# 5_cyber60-alps_periferals.net
KiCad netlist of a schematic drawn in Altium Designer
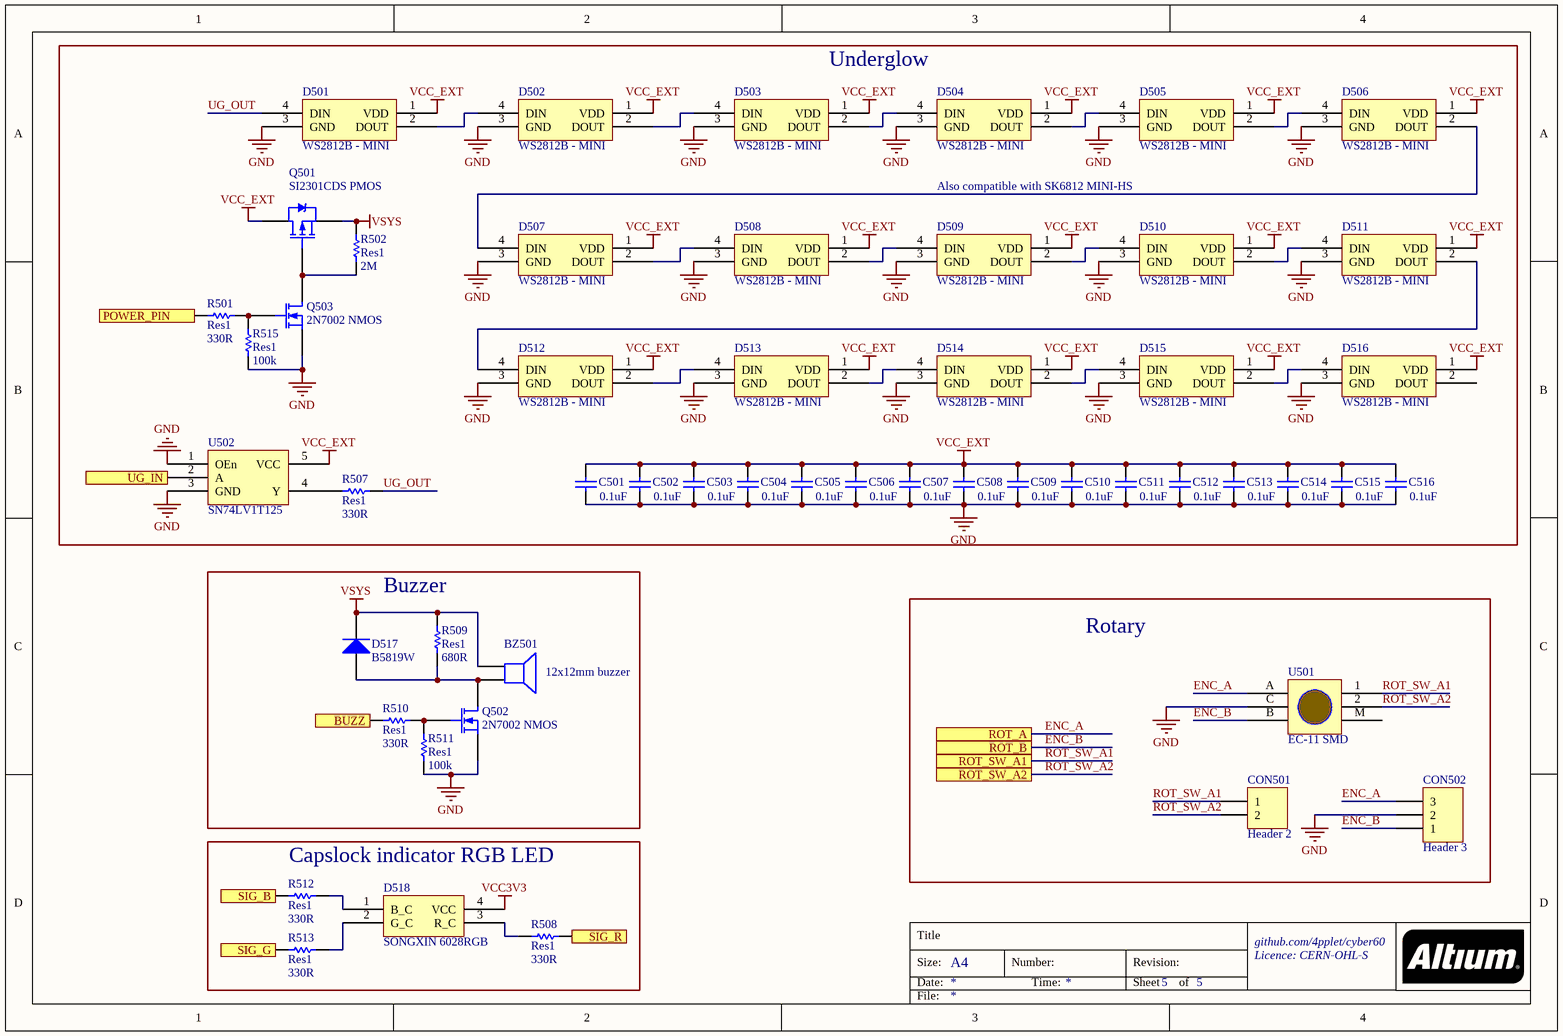
[diagram p0: 5_cyber60-alps_periferals.SchDoc]

(export (version "E")
  (design (tool "Eeschema 10.0.6"))
  (components
    (comp (ref "BZ501")
      (value "12x12mm buzzer")
      (footprint "buzzer 12x12")
      (description "Loudspeaker")
      (fields (field (name "LCSC PART #") "C409829") (field (name "MRF.PART") "YS-SBZ1230"))
      (libsource (lib "Miscellaneous Devices") (part "Speaker"))
    )
    (comp (ref "C501")
      (value "0.1uF")
      (footprint "C0603[1608]")
      (description "Capacitor")
      (fields (field (name "MFG") "KEMET") (field (name "LCSC PART #") "C14663"))
      (libsource (lib "Miscellaneous Devices") (part "Cap"))
    )
    (comp (ref "C502")
      (value "0.1uF")
      (footprint "C0603[1608]")
      (description "Capacitor")
      (fields (field (name "MFG") "KEMET") (field (name "LCSC PART #") "C14663"))
      (libsource (lib "Miscellaneous Devices") (part "Cap"))
    )
    (comp (ref "C503")
      (value "0.1uF")
      (footprint "C0603[1608]")
      (description "Capacitor")
      (fields (field (name "MFG") "KEMET") (field (name "LCSC PART #") "C14663"))
      (libsource (lib "Miscellaneous Devices") (part "Cap"))
    )
    (comp (ref "C504")
      (value "0.1uF")
      (footprint "C0603[1608]")
      (description "Capacitor")
      (fields (field (name "MFG") "KEMET") (field (name "LCSC PART #") "C14663"))
      (libsource (lib "Miscellaneous Devices") (part "Cap"))
    )
    (comp (ref "C505")
      (value "0.1uF")
      (footprint "C0603[1608]")
      (description "Capacitor")
      (fields (field (name "MFG") "KEMET") (field (name "LCSC PART #") "C14663"))
      (libsource (lib "Miscellaneous Devices") (part "Cap"))
    )
    (comp (ref "C506")
      (value "0.1uF")
      (footprint "C0603[1608]")
      (description "Capacitor")
      (fields (field (name "MFG") "KEMET") (field (name "LCSC PART #") "C14663"))
      (libsource (lib "Miscellaneous Devices") (part "Cap"))
    )
    (comp (ref "C507")
      (value "0.1uF")
      (footprint "C0603[1608]")
      (description "Capacitor")
      (fields (field (name "MFG") "KEMET") (field (name "LCSC PART #") "C14663"))
      (libsource (lib "Miscellaneous Devices") (part "Cap"))
    )
    (comp (ref "C508")
      (value "0.1uF")
      (footprint "C0603[1608]")
      (description "Capacitor")
      (fields (field (name "MFG") "KEMET") (field (name "LCSC PART #") "C14663"))
      (libsource (lib "Miscellaneous Devices") (part "Cap"))
    )
    (comp (ref "C509")
      (value "0.1uF")
      (footprint "C0603[1608]")
      (description "Capacitor")
      (fields (field (name "MFG") "KEMET") (field (name "LCSC PART #") "C14663"))
      (libsource (lib "Miscellaneous Devices") (part "Cap"))
    )
    (comp (ref "C510")
      (value "0.1uF")
      (footprint "C0603[1608]")
      (description "Capacitor")
      (fields (field (name "MFG") "KEMET") (field (name "LCSC PART #") "C14663"))
      (libsource (lib "Miscellaneous Devices") (part "Cap"))
    )
    (comp (ref "C511")
      (value "0.1uF")
      (footprint "C0603[1608]")
      (description "Capacitor")
      (fields (field (name "MFG") "KEMET") (field (name "LCSC PART #") "C14663"))
      (libsource (lib "Miscellaneous Devices") (part "Cap"))
    )
    (comp (ref "C512")
      (value "0.1uF")
      (footprint "C0603[1608]")
      (description "Capacitor")
      (fields (field (name "MFG") "KEMET") (field (name "LCSC PART #") "C14663"))
      (libsource (lib "Miscellaneous Devices") (part "Cap"))
    )
    (comp (ref "C513")
      (value "0.1uF")
      (footprint "C0603[1608]")
      (description "Capacitor")
      (fields (field (name "MFG") "KEMET") (field (name "LCSC PART #") "C14663"))
      (libsource (lib "Miscellaneous Devices") (part "Cap"))
    )
    (comp (ref "C514")
      (value "0.1uF")
      (footprint "C0603[1608]")
      (description "Capacitor")
      (fields (field (name "MFG") "KEMET") (field (name "LCSC PART #") "C14663"))
      (libsource (lib "Miscellaneous Devices") (part "Cap"))
    )
    (comp (ref "C515")
      (value "0.1uF")
      (footprint "C0603[1608]")
      (description "Capacitor")
      (fields (field (name "MFG") "KEMET") (field (name "LCSC PART #") "C14663"))
      (libsource (lib "Miscellaneous Devices") (part "Cap"))
    )
    (comp (ref "C516")
      (value "0.1uF")
      (footprint "C0603[1608]")
      (description "Capacitor")
      (fields (field (name "MFG") "KEMET") (field (name "LCSC PART #") "C14663"))
      (libsource (lib "Miscellaneous Devices") (part "Cap"))
    )
    (comp (ref "CON501")
      (value "Header 2")
      (footprint "HDR1X2")
      (description "Header, 2-Pin")
      (libsource (lib "Miscellaneous Connectors") (part "Header 2"))
    )
    (comp (ref "CON502")
      (value "Header 3")
      (footprint "HDR1X3")
      (description "Header, 3-Pin")
      (libsource (lib "Miscellaneous Connectors") (part "Header 3"))
    )
    (comp (ref "D501")
      (value "WS2812B - MINI")
      (footprint "WS2812B - 2020")
      (fields (field (name "LCSC PART #") "C965556") (field (name "MRF.PART") "WS2812C-2020"))
      (libsource (lib "Keebs") (part "WS2812B"))
    )
    (comp (ref "D502")
      (value "WS2812B - MINI")
      (footprint "WS2812B - 2020")
      (fields (field (name "LCSC PART #") "C965556") (field (name "MRF.PART") "WS2812C-2020"))
      (libsource (lib "Keebs") (part "WS2812B"))
    )
    (comp (ref "D503")
      (value "WS2812B - MINI")
      (footprint "WS2812B - 2020")
      (fields (field (name "LCSC PART #") "C965556") (field (name "MRF.PART") "WS2812C-2020"))
      (libsource (lib "Keebs") (part "WS2812B"))
    )
    (comp (ref "D504")
      (value "WS2812B - MINI")
      (footprint "WS2812B - 2020")
      (fields (field (name "LCSC PART #") "C965556") (field (name "MRF.PART") "WS2812C-2020"))
      (libsource (lib "Keebs") (part "WS2812B"))
    )
    (comp (ref "D505")
      (value "WS2812B - MINI")
      (footprint "WS2812B - 2020")
      (fields (field (name "LCSC PART #") "C965556") (field (name "MRF.PART") "WS2812C-2020"))
      (libsource (lib "Keebs") (part "WS2812B"))
    )
    (comp (ref "D506")
      (value "WS2812B - MINI")
      (footprint "WS2812B - 2020")
      (fields (field (name "LCSC PART #") "C965556") (field (name "MRF.PART") "WS2812C-2020"))
      (libsource (lib "Keebs") (part "WS2812B"))
    )
    (comp (ref "D507")
      (value "WS2812B - MINI")
      (footprint "WS2812B - 2020")
      (fields (field (name "LCSC PART #") "C965556") (field (name "MRF.PART") "WS2812C-2020"))
      (libsource (lib "Keebs") (part "WS2812B"))
    )
    (comp (ref "D508")
      (value "WS2812B - MINI")
      (footprint "WS2812B - 2020")
      (fields (field (name "LCSC PART #") "C965556") (field (name "MRF.PART") "WS2812C-2020"))
      (libsource (lib "Keebs") (part "WS2812B"))
    )
    (comp (ref "D509")
      (value "WS2812B - MINI")
      (footprint "WS2812B - 2020")
      (fields (field (name "LCSC PART #") "C965556") (field (name "MRF.PART") "WS2812C-2020"))
      (libsource (lib "Keebs") (part "WS2812B"))
    )
    (comp (ref "D510")
      (value "WS2812B - MINI")
      (footprint "WS2812B - 2020")
      (fields (field (name "LCSC PART #") "C965556") (field (name "MRF.PART") "WS2812C-2020"))
      (libsource (lib "Keebs") (part "WS2812B"))
    )
    (comp (ref "D511")
      (value "WS2812B - MINI")
      (footprint "WS2812B - 2020")
      (fields (field (name "LCSC PART #") "C965556") (field (name "MRF.PART") "WS2812C-2020"))
      (libsource (lib "Keebs") (part "WS2812B"))
    )
    (comp (ref "D512")
      (value "WS2812B - MINI")
      (footprint "WS2812B - 2020")
      (fields (field (name "LCSC PART #") "C965556") (field (name "MRF.PART") "WS2812C-2020"))
      (libsource (lib "Keebs") (part "WS2812B"))
    )
    (comp (ref "D513")
      (value "WS2812B - MINI")
      (footprint "WS2812B - 2020")
      (fields (field (name "LCSC PART #") "C965556") (field (name "MRF.PART") "WS2812C-2020"))
      (libsource (lib "Keebs") (part "WS2812B"))
    )
    (comp (ref "D514")
      (value "WS2812B - MINI")
      (footprint "WS2812B - 2020")
      (fields (field (name "LCSC PART #") "C965556") (field (name "MRF.PART") "WS2812C-2020"))
      (libsource (lib "Keebs") (part "WS2812B"))
    )
    (comp (ref "D515")
      (value "WS2812B - MINI")
      (footprint "WS2812B - 2020")
      (fields (field (name "LCSC PART #") "C965556") (field (name "MRF.PART") "WS2812C-2020"))
      (libsource (lib "Keebs") (part "WS2812B"))
    )
    (comp (ref "D516")
      (value "WS2812B - MINI")
      (footprint "WS2812B - 2020")
      (fields (field (name "LCSC PART #") "C965556") (field (name "MRF.PART") "WS2812C-2020"))
      (libsource (lib "Keebs") (part "WS2812B"))
    )
    (comp (ref "D517")
      (value "B5819W")
      (footprint "SOD-123")
      (description "Default Diode")
      (fields (field (name "LCSC PART #") "C8598"))
      (libsource (lib "Miscellaneous Devices") (part "Diode"))
    )
    (comp (ref "D518")
      (value "SONGXIN 6028RGB")
      (footprint "SONGXIN 6028RGB")
      (libsource (lib "Keebs") (part "SONGXIN 6028RGB"))
    )
    (comp (ref "Q501")
      (value "SI2301CDS PMOS")
      (footprint "SOT-23-3")
      (description "P-Channel Power MOSFET")
      (fields (field (name "MRF.PART") "SI2301CDS-T1-GE3") (field (name "LCSC PART #") "C10487"))
      (libsource (lib "Miscellaneous Devices") (part "PMOS-2"))
    )
    (comp (ref "Q502")
      (value "2N7002 NMOS")
      (footprint "SOT-23-3")
      (description "N-Channel MOSFET")
      (fields (field (name "LCSC PART #") "C8545") (field (name "MRF.PART") "2N7002"))
      (libsource (lib "Miscellaneous Devices") (part "MOSFET-N"))
    )
    (comp (ref "Q503")
      (value "2N7002 NMOS")
      (footprint "SOT-23-3")
      (description "N-Channel MOSFET")
      (fields (field (name "LCSC PART #") "C8545") (field (name "MRF.PART") "2N7002"))
      (libsource (lib "Miscellaneous Devices") (part "MOSFET-N"))
    )
    (comp (ref "R501")
      (value "Res1")
      (footprint "R0603[1608]")
      (description "Resistor")
      (fields
        (field (name "ALTIUM_VALUE") "330R")
        (field (name "LCSC PART #") "C23138")
        (field (name "MRF.PART") "0603WAF3300T5E")
      )
      (libsource (lib "Miscellaneous Devices") (part "Res1"))
    )
    (comp (ref "R502")
      (value "Res1")
      (footprint "R0603[1608]")
      (description "Resistor")
      (fields
        (field (name "ALTIUM_VALUE") "2M")
        (field (name "MRF.PART") "0603WAF2004T5E")
        (field (name "LCSC PART #") "C22976")
      )
      (libsource (lib "Miscellaneous Devices") (part "Res1"))
    )
    (comp (ref "R507")
      (value "Res1")
      (footprint "R0603[1608]")
      (description "Resistor")
      (fields
        (field (name "ALTIUM_VALUE") "330R")
        (field (name "LCSC PART #") "C23138")
        (field (name "MRF.PART") "0603WAF3300T5E")
      )
      (libsource (lib "Miscellaneous Devices") (part "Res1"))
    )
    (comp (ref "R508")
      (value "Res1")
      (footprint "R0603[1608]")
      (description "Resistor")
      (fields
        (field (name "ALTIUM_VALUE") "330R")
        (field (name "LCSC PART #") "C23138")
        (field (name "MRF.PART") "0603WAF3300T5E")
      )
      (libsource (lib "Miscellaneous Devices") (part "Res1"))
    )
    (comp (ref "R509")
      (value "Res1")
      (footprint "R0603[1608]")
      (description "Resistor")
      (fields
        (field (name "ALTIUM_VALUE") "680R")
        (field (name "MRF.PART") "0603WAF6800T5E")
        (field (name "LCSC PART #") "C23228")
      )
      (libsource (lib "Miscellaneous Devices") (part "Res1"))
    )
    (comp (ref "R510")
      (value "Res1")
      (footprint "R0603[1608]")
      (description "Resistor")
      (fields
        (field (name "ALTIUM_VALUE") "330R")
        (field (name "LCSC PART #") "C23138")
        (field (name "MRF.PART") "0603WAF3300T5E")
      )
      (libsource (lib "Miscellaneous Devices") (part "Res1"))
    )
    (comp (ref "R511")
      (value "Res1")
      (footprint "R0603[1608]")
      (description "Resistor")
      (fields
        (field (name "ALTIUM_VALUE") "100k")
        (field (name "MRF.PART") "0603WAF1003T5E")
        (field (name "LCSC PART #") "C25803")
      )
      (libsource (lib "Miscellaneous Devices") (part "Res1"))
    )
    (comp (ref "R512")
      (value "Res1")
      (footprint "R0603[1608]")
      (description "Resistor")
      (fields
        (field (name "ALTIUM_VALUE") "330R")
        (field (name "LCSC PART #") "C23138")
        (field (name "MRF.PART") "0603WAF3300T5E")
      )
      (libsource (lib "Miscellaneous Devices") (part "Res1"))
    )
    (comp (ref "R513")
      (value "Res1")
      (footprint "R0603[1608]")
      (description "Resistor")
      (fields
        (field (name "ALTIUM_VALUE") "330R")
        (field (name "LCSC PART #") "C23138")
        (field (name "MRF.PART") "0603WAF3300T5E")
      )
      (libsource (lib "Miscellaneous Devices") (part "Res1"))
    )
    (comp (ref "R515")
      (value "Res1")
      (footprint "R0603[1608]")
      (description "Resistor")
      (fields
        (field (name "ALTIUM_VALUE") "100k")
        (field (name "MRF.PART") "0603WAF1003T5E")
        (field (name "LCSC PART #") "C25803")
      )
      (libsource (lib "Miscellaneous Devices") (part "Res1"))
    )
    (comp (ref "U501") (value "EC-11 SMD") (footprint "EC11-SMD") (libsource (lib "Keebs") (part "EC-11")))
    (comp (ref "U502")
      (value "SN74LV1T125")
      (footprint "SOT-23-5")
      (description "SN74LV1T125 or SN74LV1T34. Connect OE to GND")
      (fields (field (name "LCSC PART #") "C473338") (field (name "MRF.PART") "SN74LV1T125DBVR"))
      (libsource (lib "Keebs") (part "SN74LV1T125"))
    )
  )
  (nets
    (net (code "1") (name "/BUZZ") (class "Default")
      (node (ref "R510") (pin "2") (pinfunction "2_2") (pintype "passive"))
    )
    (net (code "2") (name "/ENC_A") (class "Default")
      (node (ref "CON502") (pin "3") (pinfunction "3_3") (pintype "passive"))
      (node (ref "U501") (pin "A") (pinfunction "B_A") (pintype "passive"))
    )
    (net (code "3") (name "/ENC_B") (class "Default")
      (node (ref "CON502") (pin "1") (pinfunction "1_1") (pintype "passive"))
      (node (ref "U501") (pin "B") (pinfunction "B_B") (pintype "passive"))
    )
    (net (code "4") (name "/POWER_PIN") (class "Default")
      (node (ref "R501") (pin "1") (pinfunction "1_1") (pintype "passive"))
    )
    (net (code "5") (name "/ROT_SW_A1") (class "Default")
      (node (ref "CON501") (pin "1") (pinfunction "1_1") (pintype "passive"))
      (node (ref "U501") (pin "1") (pinfunction "1_1") (pintype "passive"))
    )
    (net (code "6") (name "/ROT_SW_A2") (class "Default")
      (node (ref "CON501") (pin "2") (pinfunction "2_2") (pintype "passive"))
      (node (ref "U501") (pin "2") (pinfunction "2_2") (pintype "passive"))
    )
    (net (code "7") (name "/SIG_B") (class "Default")
      (node (ref "R512") (pin "2") (pinfunction "2_2") (pintype "passive"))
    )
    (net (code "8") (name "/SIG_G") (class "Default")
      (node (ref "R513") (pin "2") (pinfunction "2_2") (pintype "passive"))
    )
    (net (code "9") (name "/SIG_R") (class "Default")
      (node (ref "R508") (pin "1") (pinfunction "1_1") (pintype "passive"))
    )
    (net (code "10") (name "/UG_IN") (class "Default")
      (node (ref "U502") (pin "2") (pinfunction "A_2") (pintype "passive"))
    )
    (net (code "11") (name "/UG_OUT") (class "Default")
      (node (ref "D501") (pin "4") (pinfunction "DIN_4") (pintype "passive"))
      (node (ref "R507") (pin "1") (pinfunction "1_1") (pintype "passive"))
    )
    (net (code "12") (name "GND") (class "Default")
      (node (ref "C501") (pin "1") (pinfunction "1_1") (pintype "passive"))
      (node (ref "C502") (pin "1") (pinfunction "1_1") (pintype "passive"))
      (node (ref "C503") (pin "1") (pinfunction "1_1") (pintype "passive"))
      (node (ref "C504") (pin "1") (pinfunction "1_1") (pintype "passive"))
      (node (ref "C505") (pin "1") (pinfunction "1_1") (pintype "passive"))
      (node (ref "C506") (pin "1") (pinfunction "1_1") (pintype "passive"))
      (node (ref "C507") (pin "1") (pinfunction "1_1") (pintype "passive"))
      (node (ref "C508") (pin "1") (pinfunction "1_1") (pintype "passive"))
      (node (ref "C509") (pin "1") (pinfunction "1_1") (pintype "passive"))
      (node (ref "C510") (pin "1") (pinfunction "1_1") (pintype "passive"))
      (node (ref "C511") (pin "1") (pinfunction "1_1") (pintype "passive"))
      (node (ref "C512") (pin "1") (pinfunction "1_1") (pintype "passive"))
      (node (ref "C513") (pin "1") (pinfunction "1_1") (pintype "passive"))
      (node (ref "C514") (pin "1") (pinfunction "1_1") (pintype "passive"))
      (node (ref "C515") (pin "1") (pinfunction "1_1") (pintype "passive"))
      (node (ref "C516") (pin "1") (pinfunction "1_1") (pintype "passive"))
      (node (ref "CON502") (pin "2") (pinfunction "2_2") (pintype "passive"))
      (node (ref "D501") (pin "3") (pinfunction "GND_3") (pintype "passive"))
      (node (ref "D502") (pin "3") (pinfunction "GND_3") (pintype "passive"))
      (node (ref "D503") (pin "3") (pinfunction "GND_3") (pintype "passive"))
      (node (ref "D504") (pin "3") (pinfunction "GND_3") (pintype "passive"))
      (node (ref "D505") (pin "3") (pinfunction "GND_3") (pintype "passive"))
      (node (ref "D506") (pin "3") (pinfunction "GND_3") (pintype "passive"))
      (node (ref "D507") (pin "3") (pinfunction "GND_3") (pintype "passive"))
      (node (ref "D508") (pin "3") (pinfunction "GND_3") (pintype "passive"))
      (node (ref "D509") (pin "3") (pinfunction "GND_3") (pintype "passive"))
      (node (ref "D510") (pin "3") (pinfunction "GND_3") (pintype "passive"))
      (node (ref "D511") (pin "3") (pinfunction "GND_3") (pintype "passive"))
      (node (ref "D512") (pin "3") (pinfunction "GND_3") (pintype "passive"))
      (node (ref "D513") (pin "3") (pinfunction "GND_3") (pintype "passive"))
      (node (ref "D514") (pin "3") (pinfunction "GND_3") (pintype "passive"))
      (node (ref "D515") (pin "3") (pinfunction "GND_3") (pintype "passive"))
      (node (ref "D516") (pin "3") (pinfunction "GND_3") (pintype "passive"))
      (node (ref "Q502") (pin "2") (pinfunction "S_2") (pintype "passive"))
      (node (ref "Q503") (pin "2") (pinfunction "S_2") (pintype "passive"))
      (node (ref "R511") (pin "2") (pinfunction "2_2") (pintype "passive"))
      (node (ref "R515") (pin "2") (pinfunction "2_2") (pintype "passive"))
      (node (ref "U501") (pin "C") (pinfunction "C_C") (pintype "passive"))
      (node (ref "U502") (pin "1") (pinfunction "OEn_1") (pintype "passive"))
      (node (ref "U502") (pin "3") (pinfunction "GND_3") (pintype "passive"))
    )
    (net (code "13") (name "Net-(D501-DOUT)") (class "Default")
      (node (ref "D501") (pin "2") (pinfunction "DOUT_2") (pintype "passive"))
      (node (ref "D502") (pin "4") (pinfunction "DIN_4") (pintype "passive"))
    )
    (net (code "14") (name "Net-(D502-DOUT)") (class "Default")
      (node (ref "D502") (pin "2") (pinfunction "DOUT_2") (pintype "passive"))
      (node (ref "D503") (pin "4") (pinfunction "DIN_4") (pintype "passive"))
    )
    (net (code "15") (name "Net-(D503-DOUT)") (class "Default")
      (node (ref "D503") (pin "2") (pinfunction "DOUT_2") (pintype "passive"))
      (node (ref "D504") (pin "4") (pinfunction "DIN_4") (pintype "passive"))
    )
    (net (code "16") (name "Net-(D504-DOUT)") (class "Default")
      (node (ref "D504") (pin "2") (pinfunction "DOUT_2") (pintype "passive"))
      (node (ref "D505") (pin "4") (pinfunction "DIN_4") (pintype "passive"))
    )
    (net (code "17") (name "Net-(D505-DOUT)") (class "Default")
      (node (ref "D505") (pin "2") (pinfunction "DOUT_2") (pintype "passive"))
      (node (ref "D506") (pin "4") (pinfunction "DIN_4") (pintype "passive"))
    )
    (net (code "18") (name "Net-(D506-DOUT)") (class "Default")
      (node (ref "D506") (pin "2") (pinfunction "DOUT_2") (pintype "passive"))
      (node (ref "D507") (pin "4") (pinfunction "DIN_4") (pintype "passive"))
    )
    (net (code "19") (name "Net-(D507-DOUT)") (class "Default")
      (node (ref "D507") (pin "2") (pinfunction "DOUT_2") (pintype "passive"))
      (node (ref "D508") (pin "4") (pinfunction "DIN_4") (pintype "passive"))
    )
    (net (code "20") (name "Net-(D508-DOUT)") (class "Default")
      (node (ref "D508") (pin "2") (pinfunction "DOUT_2") (pintype "passive"))
      (node (ref "D509") (pin "4") (pinfunction "DIN_4") (pintype "passive"))
    )
    (net (code "21") (name "Net-(D509-DOUT)") (class "Default")
      (node (ref "D509") (pin "2") (pinfunction "DOUT_2") (pintype "passive"))
      (node (ref "D510") (pin "4") (pinfunction "DIN_4") (pintype "passive"))
    )
    (net (code "22") (name "Net-(D510-DOUT)") (class "Default")
      (node (ref "D510") (pin "2") (pinfunction "DOUT_2") (pintype "passive"))
      (node (ref "D511") (pin "4") (pinfunction "DIN_4") (pintype "passive"))
    )
    (net (code "23") (name "Net-(D511-DOUT)") (class "Default")
      (node (ref "D511") (pin "2") (pinfunction "DOUT_2") (pintype "passive"))
      (node (ref "D512") (pin "4") (pinfunction "DIN_4") (pintype "passive"))
    )
    (net (code "24") (name "Net-(D512-DOUT)") (class "Default")
      (node (ref "D512") (pin "2") (pinfunction "DOUT_2") (pintype "passive"))
      (node (ref "D513") (pin "4") (pinfunction "DIN_4") (pintype "passive"))
    )
    (net (code "25") (name "Net-(D513-DOUT)") (class "Default")
      (node (ref "D513") (pin "2") (pinfunction "DOUT_2") (pintype "passive"))
      (node (ref "D514") (pin "4") (pinfunction "DIN_4") (pintype "passive"))
    )
    (net (code "26") (name "Net-(D514-DOUT)") (class "Default")
      (node (ref "D514") (pin "2") (pinfunction "DOUT_2") (pintype "passive"))
      (node (ref "D515") (pin "4") (pinfunction "DIN_4") (pintype "passive"))
    )
    (net (code "27") (name "Net-(D515-DOUT)") (class "Default")
      (node (ref "D515") (pin "2") (pinfunction "DOUT_2") (pintype "passive"))
      (node (ref "D516") (pin "4") (pinfunction "DIN_4") (pintype "passive"))
    )
    (net (code "28") (name "Net-(D517-A)") (class "Default")
      (node (ref "BZ501") (pin "2") (pinfunction "2_2") (pintype "passive"))
      (node (ref "D517") (pin "1") (pinfunction "A_1") (pintype "passive"))
      (node (ref "Q502") (pin "3") (pinfunction "D_3") (pintype "passive"))
      (node (ref "R509") (pin "2") (pinfunction "2_2") (pintype "passive"))
    )
    (net (code "29") (name "Net-(D518-B_C)") (class "Default")
      (node (ref "D518") (pin "1") (pinfunction "B_C_1") (pintype "passive"))
      (node (ref "R512") (pin "1") (pinfunction "1_1") (pintype "passive"))
    )
    (net (code "30") (name "Net-(D518-G_C)") (class "Default")
      (node (ref "D518") (pin "2") (pinfunction "G_C_2") (pintype "passive"))
      (node (ref "R513") (pin "1") (pinfunction "1_1") (pintype "passive"))
    )
    (net (code "31") (name "Net-(D518-R_C)") (class "Default")
      (node (ref "D518") (pin "3") (pinfunction "R_C_3") (pintype "passive"))
      (node (ref "R508") (pin "2") (pinfunction "2_2") (pintype "passive"))
    )
    (net (code "32") (name "Net-(Q501-G)") (class "Default")
      (node (ref "Q501") (pin "1") (pinfunction "G_1") (pintype "passive"))
      (node (ref "Q503") (pin "3") (pinfunction "D_3") (pintype "passive"))
      (node (ref "R502") (pin "1") (pinfunction "1_1") (pintype "passive"))
    )
    (net (code "33") (name "Net-(Q502-G)") (class "Default")
      (node (ref "Q502") (pin "1") (pinfunction "G_1") (pintype "passive"))
      (node (ref "R510") (pin "1") (pinfunction "1_1") (pintype "passive"))
      (node (ref "R511") (pin "1") (pinfunction "1_1") (pintype "passive"))
    )
    (net (code "34") (name "Net-(Q503-G)") (class "Default")
      (node (ref "Q503") (pin "1") (pinfunction "G_1") (pintype "passive"))
      (node (ref "R501") (pin "2") (pinfunction "2_2") (pintype "passive"))
      (node (ref "R515") (pin "1") (pinfunction "1_1") (pintype "passive"))
    )
    (net (code "35") (name "Net-(U502-Y)") (class "Default")
      (node (ref "R507") (pin "2") (pinfunction "2_2") (pintype "passive"))
      (node (ref "U502") (pin "4") (pinfunction "Y_4") (pintype "passive"))
    )
    (net (code "36") (name "VCC3V3") (class "Default")
      (node (ref "D518") (pin "4") (pinfunction "VCC_4") (pintype "passive"))
    )
    (net (code "37") (name "VCC_EXT") (class "Default")
      (node (ref "C501") (pin "2") (pinfunction "2_2") (pintype "passive"))
      (node (ref "C502") (pin "2") (pinfunction "2_2") (pintype "passive"))
      (node (ref "C503") (pin "2") (pinfunction "2_2") (pintype "passive"))
      (node (ref "C504") (pin "2") (pinfunction "2_2") (pintype "passive"))
      (node (ref "C505") (pin "2") (pinfunction "2_2") (pintype "passive"))
      (node (ref "C506") (pin "2") (pinfunction "2_2") (pintype "passive"))
      (node (ref "C507") (pin "2") (pinfunction "2_2") (pintype "passive"))
      (node (ref "C508") (pin "2") (pinfunction "2_2") (pintype "passive"))
      (node (ref "C509") (pin "2") (pinfunction "2_2") (pintype "passive"))
      (node (ref "C510") (pin "2") (pinfunction "2_2") (pintype "passive"))
      (node (ref "C511") (pin "2") (pinfunction "2_2") (pintype "passive"))
      (node (ref "C512") (pin "2") (pinfunction "2_2") (pintype "passive"))
      (node (ref "C513") (pin "2") (pinfunction "2_2") (pintype "passive"))
      (node (ref "C514") (pin "2") (pinfunction "2_2") (pintype "passive"))
      (node (ref "C515") (pin "2") (pinfunction "2_2") (pintype "passive"))
      (node (ref "C516") (pin "2") (pinfunction "2_2") (pintype "passive"))
      (node (ref "D501") (pin "1") (pinfunction "VDD_1") (pintype "passive"))
      (node (ref "D502") (pin "1") (pinfunction "VDD_1") (pintype "passive"))
      (node (ref "D503") (pin "1") (pinfunction "VDD_1") (pintype "passive"))
      (node (ref "D504") (pin "1") (pinfunction "VDD_1") (pintype "passive"))
      (node (ref "D505") (pin "1") (pinfunction "VDD_1") (pintype "passive"))
      (node (ref "D506") (pin "1") (pinfunction "VDD_1") (pintype "passive"))
      (node (ref "D507") (pin "1") (pinfunction "VDD_1") (pintype "passive"))
      (node (ref "D508") (pin "1") (pinfunction "VDD_1") (pintype "passive"))
      (node (ref "D509") (pin "1") (pinfunction "VDD_1") (pintype "passive"))
      (node (ref "D510") (pin "1") (pinfunction "VDD_1") (pintype "passive"))
      (node (ref "D511") (pin "1") (pinfunction "VDD_1") (pintype "passive"))
      (node (ref "D512") (pin "1") (pinfunction "VDD_1") (pintype "passive"))
      (node (ref "D513") (pin "1") (pinfunction "VDD_1") (pintype "passive"))
      (node (ref "D514") (pin "1") (pinfunction "VDD_1") (pintype "passive"))
      (node (ref "D515") (pin "1") (pinfunction "VDD_1") (pintype "passive"))
      (node (ref "D516") (pin "1") (pinfunction "VDD_1") (pintype "passive"))
      (node (ref "Q501") (pin "3") (pinfunction "D_3") (pintype "passive"))
      (node (ref "U502") (pin "5") (pinfunction "VCC_5") (pintype "passive"))
    )
    (net (code "38") (name "VSYS") (class "Default")
      (node (ref "BZ501") (pin "1") (pinfunction "1_1") (pintype "passive"))
      (node (ref "D517") (pin "2") (pinfunction "K_2") (pintype "passive"))
      (node (ref "Q501") (pin "2") (pinfunction "S_2") (pintype "passive"))
      (node (ref "R502") (pin "2") (pinfunction "2_2") (pintype "passive"))
      (node (ref "R509") (pin "1") (pinfunction "1_1") (pintype "passive"))
    )
    (net (code "39") (name "unconnected-(D516-DOUT-Pad2)") (class "Default")
      (node (ref "D516") (pin "2") (pinfunction "DOUT_2") (pintype "passive"))
    )
    (net (code "40") (name "unconnected-(U501-PadM)") (class "Default")
      (node (ref "U501") (pin "M") (pinfunction "M_M") (pintype "passive"))
    )
  )
)
